# CAN.net
KiCad netlist of a schematic drawn in Altium Designer
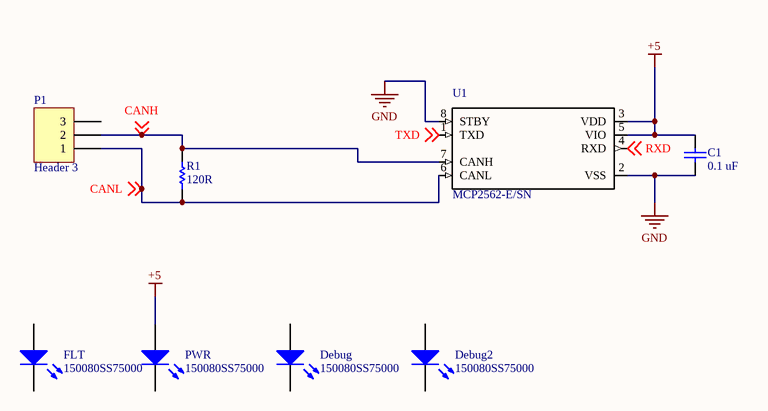
[diagram p0: CAN.SchDoc]

(export (version "E")
  (design (tool "Eeschema 10.0.6"))
  (components
    (comp (ref "C1")
      (value "0.1 uF")
      (footprint "CAPC2013X140X50LL20T25")
      (description "Chip Capacitor, 2.2 uF, +/- 10%, 10 V, -55 to 85 degC, 0805 (2012 Metric), RoHS, Tape and Reel")
      (fields (field (name "MANUFACTURER") "AVX"))
      (libsource (lib "Altium Content Vault") (part "CAP-NP-2"))
    )
    (comp (ref "Debug")
      (value "150080SS75000")
      (footprint "0805_A")
      (description "SMD mono-color Chip LED, WL-SMCW, Super Red")
      (fields (field (name "MANUFACTURER") "Wuerth Elektronik"))
      (libsource (lib "Altium Content Vault") (part "WE-LED_K1A2-2"))
    )
    (comp (ref "Debug2")
      (value "150080SS75000")
      (footprint "0805_A")
      (description "SMD mono-color Chip LED, WL-SMCW, Super Red")
      (fields (field (name "MANUFACTURER") "Wuerth Elektronik"))
      (libsource (lib "Altium Content Vault") (part "WE-LED_K1A2-2"))
    )
    (comp (ref "FLT")
      (value "150080SS75000")
      (footprint "0805_A")
      (description "SMD mono-color Chip LED, WL-SMCW, Super Red")
      (fields (field (name "MANUFACTURER") "Wuerth Elektronik"))
      (libsource (lib "Altium Content Vault") (part "WE-LED_K1A2-2"))
    )
    (comp (ref "P1")
      (value "Header 3")
      (footprint "HDR1X3")
      (description "Header, 3-Pin")
      (fields (field (name "PUBLISHER") "Altium Limited"))
      (libsource (lib "Miscellaneous Connectors") (part "Header 3"))
    )
    (comp (ref "PWR")
      (value "150080SS75000")
      (footprint "0805_A")
      (description "SMD mono-color Chip LED, WL-SMCW, Super Red")
      (fields (field (name "MANUFACTURER") "Wuerth Elektronik"))
      (libsource (lib "Altium Content Vault") (part "WE-LED_K1A2-2"))
    )
    (comp (ref "R1")
      (value "120R")
      (footprint "RESC0805(2012)_N")
      (description "Generic 0805 Resistor")
      (fields (field (name "TOLERANCE") "5 %") (field (name "POWER") "0.125 W"))
      (libsource (lib "Husky Robotics Standard Library 2019-2020") (part "Resistor 0805"))
    )
    (comp (ref "U1")
      (value "MCP2562-E/SN")
      (footprint "SOIC127P600X175-8N")
      (description "Microchip MCP2562-E/SN, CAN Transceiver 1MBps 1-channel IEC 61000-4-2, 8-Pin SOIC")
      (fields (field (name "MF") "Microchip"))
      (libsource (lib "Husky Robotics Standard Library 2019-2020") (part "CAN Tranceiver"))
    )
  )
  (nets
    (net (code "1") (name "+5") (class "Default")
      (node (ref "C1") (pin "1") (pinfunction "1_1") (pintype "passive"))
      (node (ref "PWR") (pin "2") (pinfunction "A_2") (pintype "passive"))
      (node (ref "U1") (pin "3") (pinfunction "VDD_3") (pintype "power_in"))
      (node (ref "U1") (pin "5") (pinfunction "VIO_5") (pintype "power_in"))
    )
    (net (code "2") (name "CANH") (class "Default")
      (node (ref "P1") (pin "2") (pinfunction "2_2") (pintype "passive"))
      (node (ref "R1") (pin "2") (pinfunction "2_2") (pintype "passive"))
      (node (ref "U1") (pin "7") (pinfunction "CANH_7") (pintype "input"))
    )
    (net (code "3") (name "CANL") (class "Default")
      (node (ref "P1") (pin "1") (pinfunction "1_1") (pintype "passive"))
      (node (ref "R1") (pin "1") (pinfunction "1_1") (pintype "passive"))
      (node (ref "U1") (pin "6") (pinfunction "CANL_6") (pintype "input"))
    )
    (net (code "4") (name "GND") (class "Default")
      (node (ref "C1") (pin "2") (pinfunction "2_2") (pintype "passive"))
      (node (ref "U1") (pin "2") (pinfunction "VSS_2") (pintype "power_in"))
      (node (ref "U1") (pin "8") (pinfunction "STBY_8") (pintype "input"))
    )
    (net (code "5") (name "RXD") (class "Default")
      (node (ref "U1") (pin "4") (pinfunction "RXD_4") (pintype "output"))
    )
    (net (code "6") (name "TXD") (class "Default")
      (node (ref "U1") (pin "1") (pinfunction "TXD_1") (pintype "input"))
    )
    (net (code "7") (name "unconnected-(Debug-A-Pad2)") (class "Default")
      (node (ref "Debug") (pin "2") (pinfunction "A_2") (pintype "passive"))
    )
    (net (code "8") (name "unconnected-(Debug-K-Pad1)") (class "Default")
      (node (ref "Debug") (pin "1") (pinfunction "K_1") (pintype "passive"))
    )
    (net (code "9") (name "unconnected-(Debug2-A-Pad2)") (class "Default")
      (node (ref "Debug2") (pin "2") (pinfunction "A_2") (pintype "passive"))
    )
    (net (code "10") (name "unconnected-(Debug2-K-Pad1)") (class "Default")
      (node (ref "Debug2") (pin "1") (pinfunction "K_1") (pintype "passive"))
    )
    (net (code "11") (name "unconnected-(FLT-A-Pad2)") (class "Default")
      (node (ref "FLT") (pin "2") (pinfunction "A_2") (pintype "passive"))
    )
    (net (code "12") (name "unconnected-(FLT-K-Pad1)") (class "Default")
      (node (ref "FLT") (pin "1") (pinfunction "K_1") (pintype "passive"))
    )
    (net (code "13") (name "unconnected-(P1-Pad3)") (class "Default")
      (node (ref "P1") (pin "3") (pinfunction "3_3") (pintype "passive"))
    )
    (net (code "14") (name "unconnected-(PWR-K-Pad1)") (class "Default")
      (node (ref "PWR") (pin "1") (pinfunction "K_1") (pintype "passive"))
    )
  )
)
